# TL200.net
KiCad netlist of a schematic drawn in Altium Designer
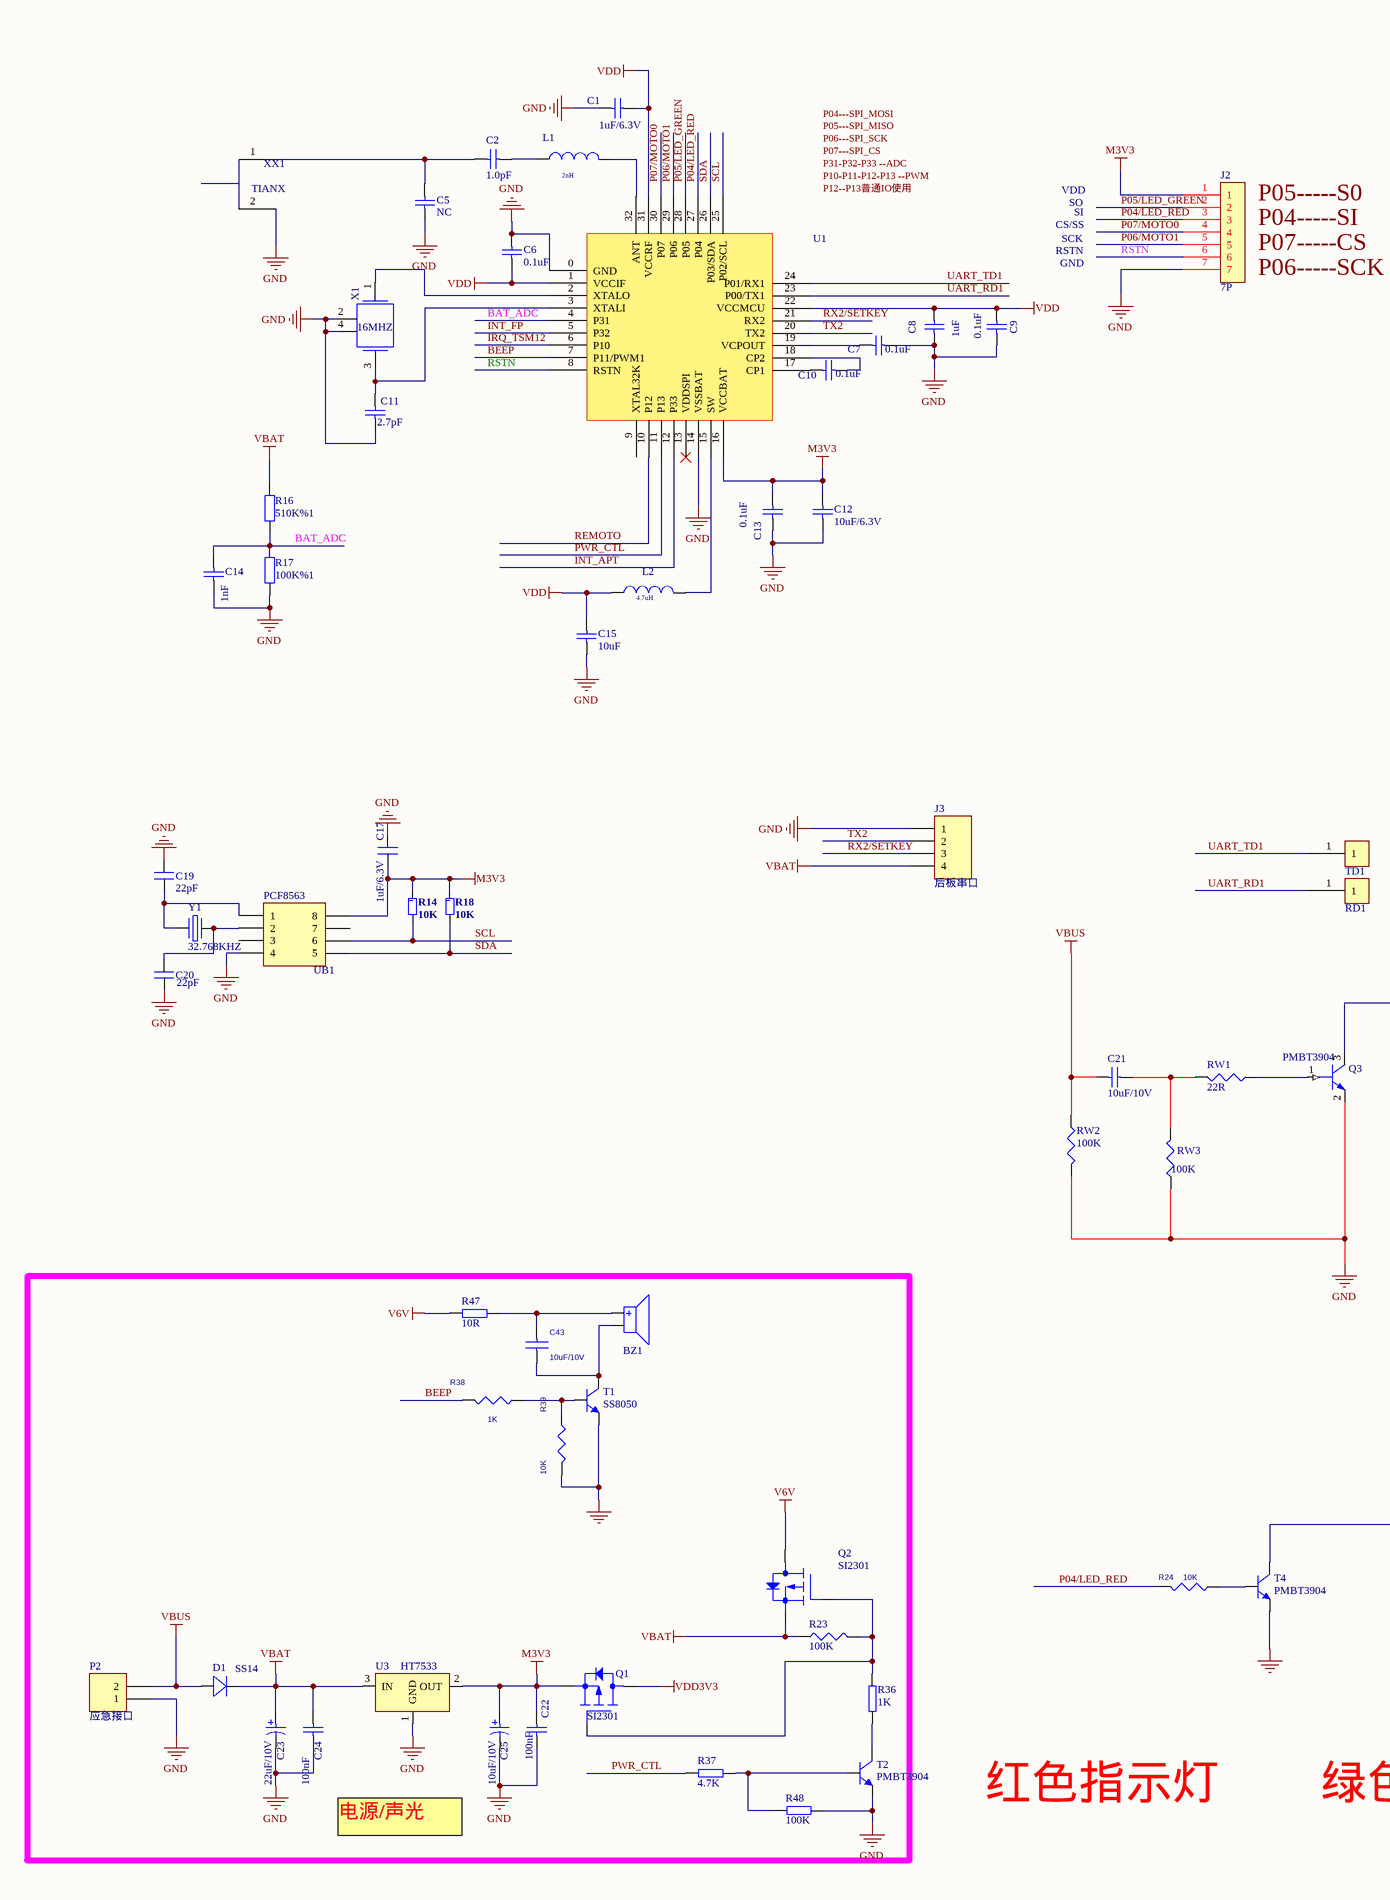
[diagram p0: TL200蓝牙主板.SchDoc, left]
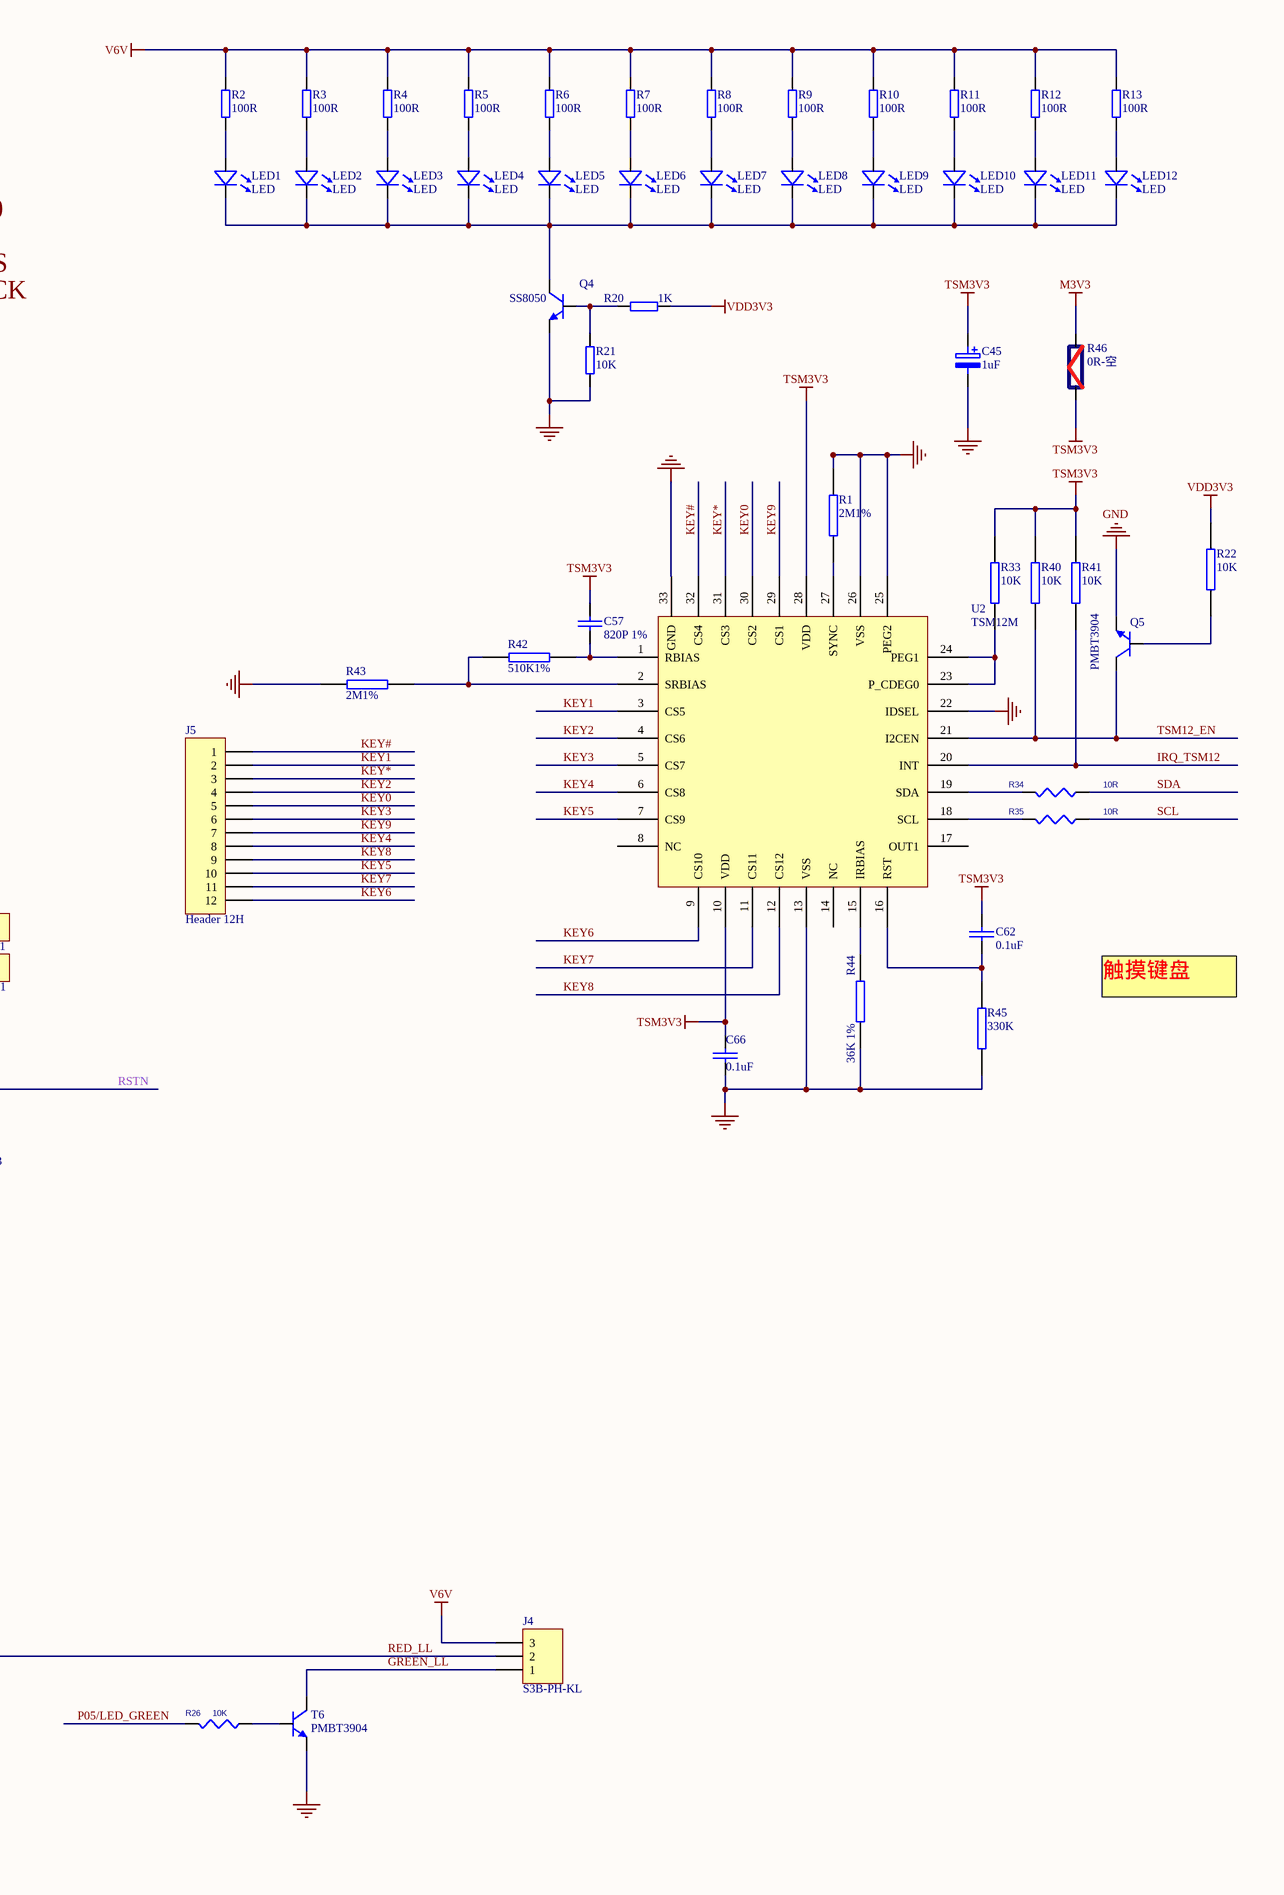
[diagram p1: TL200蓝牙主板.SchDoc, right]

(export (version "E")
  (design (tool "Eeschema 10.0.6"))
  (components
    (comp (ref "BZ1")
      (value "BUZZER")
      (footprint "BUZZER_D93_L40")
      (description "Buzzer")
      (libsource (lib "MyLibrary") (part "BUZZER"))
    )
    (comp (ref "C1")
      (value "1uF/6.3V")
      (footprint "LC-0402_C")
      (description "Capacitor")
      (fields (field (name "PUBLISHER") "Altium Limited"))
      (libsource (lib "MySchlib") (part "Cap"))
    )
    (comp (ref "C2")
      (value "1.0pF")
      (footprint "LC-0402_C")
      (description "Capacitor")
      (fields (field (name "PUBLISHER") "Altium Limited"))
      (libsource (lib "MySchlib") (part "Cap"))
    )
    (comp (ref "C5")
      (value "NC")
      (footprint "LC-0402_C")
      (description "Capacitor")
      (fields (field (name "PUBLISHER") "Altium Limited"))
      (libsource (lib "MySchlib") (part "Cap"))
    )
    (comp (ref "C6")
      (value "0.1uF")
      (footprint "LC-0402_C")
      (description "Capacitor")
      (fields (field (name "PUBLISHER") "Altium Limited"))
      (libsource (lib "MySchlib") (part "Cap"))
    )
    (comp (ref "C7")
      (value "0.1uF")
      (footprint "LC-0402_C")
      (description "Capacitor")
      (fields (field (name "PUBLISHER") "Altium Limited"))
      (libsource (lib "MySchlib") (part "Cap"))
    )
    (comp (ref "C8")
      (value "1uF")
      (footprint "LC-0402_C")
      (description "Capacitor")
      (fields (field (name "PUBLISHER") "Altium Limited"))
      (libsource (lib "MySchlib") (part "Cap"))
    )
    (comp (ref "C9")
      (value "0.1uF")
      (footprint "LC-0402_C")
      (description "Capacitor")
      (fields (field (name "PUBLISHER") "Altium Limited"))
      (libsource (lib "MySchlib") (part "Cap"))
    )
    (comp (ref "C10")
      (value "0.1uF")
      (footprint "LC-0402_C")
      (description "Capacitor")
      (fields (field (name "PUBLISHER") "Altium Limited"))
      (libsource (lib "MySchlib") (part "Cap"))
    )
    (comp (ref "C11")
      (value "2.7pF")
      (footprint "LC-0402_C")
      (description "Capacitor")
      (fields (field (name "PUBLISHER") "Altium Limited"))
      (libsource (lib "MySchlib") (part "Cap"))
    )
    (comp (ref "C12")
      (value "10uF/6.3V")
      (footprint "LC-0603_C")
      (description "Capacitor")
      (fields (field (name "PUBLISHER") "Altium Limited"))
      (libsource (lib "MySchlib") (part "Cap"))
    )
    (comp (ref "C13")
      (value "0.1uF")
      (footprint "LC-0402_C")
      (description "Capacitor")
      (fields (field (name "PUBLISHER") "Altium Limited"))
      (libsource (lib "MySchlib") (part "Cap"))
    )
    (comp (ref "C14")
      (value "1nF")
      (footprint "LC-0402_C")
      (description "Capacitor, Ceramic")
      (fields (field (name "TOLERANCE") "5 %"))
      (libsource (lib "MyLibrary") (part "CAP-NP"))
    )
    (comp (ref "C15")
      (value "10uF")
      (footprint "LC-0402_C")
      (description "Capacitor")
      (fields (field (name "PUBLISHER") "Altium Limited"))
      (libsource (lib "MySchlib") (part "Cap"))
    )
    (comp (ref "C17") (value "1uF/6.3V") (footprint "LC-0603_C") (libsource (lib "自建元件库") (part "C")))
    (comp (ref "C19") (value "22pF") (footprint "LC-0603_C") (libsource (lib "自建元件库") (part "C")))
    (comp (ref "C20") (value "22pF") (footprint "LC-0603_C") (libsource (lib "自建元件库") (part "C")))
    (comp (ref "C21")
      (value "10uF/10V")
      (footprint "LC-0603_C")
      (description "Capacitor, Ceramic")
      (fields (field (name "TOLERANCE") "5 %"))
      (libsource (lib "MyLibrary") (part "CAP-NP"))
    )
    (comp (ref "C22")
      (value "100nF")
      (footprint "LC-0603_C")
      (description "Capacitor, Ceramic")
      (fields (field (name "TOLERANCE") "5 %"))
      (libsource (lib "MyLibrary") (part "CAP-NP"))
    )
    (comp (ref "C23")
      (value "22uF/10V")
      (footprint "LC-0805_C")
      (description "Capacitor, tolerance ±20%")
      (libsource (lib "MySchLib") (part "CAP-P"))
    )
    (comp (ref "C24")
      (value "100nF")
      (footprint "LC-0603_C")
      (description "Capacitor, Ceramic")
      (fields (field (name "TOLERANCE") "5 %"))
      (libsource (lib "MyLibrary") (part "CAP-NP"))
    )
    (comp (ref "C25")
      (value "10uF/10V")
      (footprint "LC-0805_C")
      (description "Capacitor, tolerance ±20%")
      (libsource (lib "MySchLib") (part "CAP-P"))
    )
    (comp (ref "C43") (value "10uF/10V") (footprint "LC-0603_C") (libsource (lib "*") (part "C_0_Dup1")))
    (comp (ref "C45")
      (value "1uF")
      (footprint "LC-0603_C")
      (description "Electrolytic Capacitor")
      (libsource (lib "*") (part "C-C型"))
    )
    (comp (ref "C57")
      (value "820P 1%")
      (footprint "LC-0402_C")
      (description "Capacitor")
      (libsource (lib "*") (part "CAP"))
    )
    (comp (ref "C62")
      (value "0.1uF")
      (footprint "LC-0402_C")
      (description "Capacitor")
      (libsource (lib "*") (part "CAP"))
    )
    (comp (ref "C66")
      (value "0.1uF")
      (footprint "LC-0402_C")
      (description "Capacitor")
      (libsource (lib "*") (part "CAP"))
    )
    (comp (ref "D1") (value "SS14") (footprint "DO-214AA") (libsource (lib "MySch") (part "D")))
    (comp (ref "J2") (value "7P") (footprint "7P-2.0MM") (libsource (lib "保险箱STM32") (part "7P")))
    (comp (ref "J3")
      (value "后板串口")
      (footprint "4P-2.0XX")
      (description "Header, 4-Pin, Right Angle")
      (fields (field (name "PUBLISHER") "Altium Limited"))
      (libsource (lib "Miscellaneous Connectors") (part "Header 4H"))
    )
    (comp (ref "J4")
      (value "S3B-PH-KL")
      (footprint "3P-1.25mm-SMT")
      (description "Header, 3-Pin")
      (fields (field (name "PUBLISHER") "Altium Limited"))
      (libsource (lib "Miscellaneous Connectors") (part "Header 3"))
    )
    (comp (ref "J5")
      (value "Header 12H")
      (footprint "6P*2*1.27MM_1")
      (description "Header, 12-Pin, Right Angle")
      (fields (field (name "PUBLISHER") "Altium Limited"))
      (libsource (lib "Miscellaneous Connectors") (part "Header 12H"))
    )
    (comp (ref "L1")
      (value "2nH")
      (footprint "LC-0402_L")
      (description "Power Inductor, 4.7uH, 0.7A, 260mR DCR")
      (fields
        (field (name "XMOS PART NUMBER") "E-09-0011")
        (field (name "MANUFACTURER") "Taiyo Yuden")
        (field (name "PART CREATOR") "JG")
        (field (name "APPROVED") "NO")
      )
      (libsource (lib "MySchlib") (part "INDUCTOR"))
    )
    (comp (ref "L2")
      (value "4.7uH")
      (footprint "LC-0603_L")
      (description "Power Inductor, 4.7uH, 0.7A, 260mR DCR")
      (fields
        (field (name "XMOS PART NUMBER") "E-09-0011")
        (field (name "MANUFACTURER") "Taiyo Yuden")
        (field (name "PART CREATOR") "JG")
        (field (name "APPROVED") "NO")
      )
      (libsource (lib "MySchlib") (part "INDUCTOR"))
    )
    (comp (ref "LED1") (value "LED") (footprint "0603LED") (libsource (lib "MyLibrary") (part "LED")))
    (comp (ref "LED2") (value "LED") (footprint "0603LED") (libsource (lib "MyLibrary") (part "LED")))
    (comp (ref "LED3") (value "LED") (footprint "0603LED") (libsource (lib "MyLibrary") (part "LED")))
    (comp (ref "LED4") (value "LED") (footprint "0603LED") (libsource (lib "MyLibrary") (part "LED")))
    (comp (ref "LED5") (value "LED") (footprint "0603LED") (libsource (lib "MyLibrary") (part "LED")))
    (comp (ref "LED6") (value "LED") (footprint "0603LED") (libsource (lib "MyLibrary") (part "LED")))
    (comp (ref "LED7") (value "LED") (footprint "0603LED") (libsource (lib "MyLibrary") (part "LED")))
    (comp (ref "LED8") (value "LED") (footprint "0603LED") (libsource (lib "MyLibrary") (part "LED")))
    (comp (ref "LED9") (value "LED") (footprint "0603LED") (libsource (lib "MyLibrary") (part "LED")))
    (comp (ref "LED10") (value "LED") (footprint "0603LED") (libsource (lib "MyLibrary") (part "LED")))
    (comp (ref "LED11") (value "LED") (footprint "0603LED") (libsource (lib "MyLibrary") (part "LED")))
    (comp (ref "LED12") (value "LED") (footprint "0603LED") (libsource (lib "MyLibrary") (part "LED")))
    (comp (ref "P2")
      (value "应急接口")
      (footprint "2PIN-2.0")
      (description "Header, 2-Pin")
      (fields (field (name "PUBLISHER") "Altium Limited"))
      (libsource (lib "Miscellaneous Connectors") (part "Header 2"))
    )
    (comp (ref "Q1")
      (value "SI2301")
      (footprint "SOT-23 - GDS")
      (libsource (lib "*") (part "PWRMOSFET_EP_DGS_0"))
    )
    (comp (ref "Q2")
      (value "SI2301")
      (footprint "SOT-23 - GDS")
      (libsource (lib "*") (part "PWRMOSFET_EP_DGS_0"))
    )
    (comp (ref "Q3") (value "PMBT3904") (footprint "SOT-23-3L") (libsource (lib "*") (part "PMBT3904")))
    (comp (ref "Q4")
      (value "SS8050")
      (footprint "SOT-23-3L")
      (description "Bipolar Junction Transistor")
      (libsource (lib "MyLibrary") (part "NPN_BJT"))
    )
    (comp (ref "Q5")
      (value "PMBT3904")
      (footprint "SOT-23-3L")
      (description "Bipolar Junction Transistor")
      (libsource (lib "MyLibrary") (part "NPN_BJT"))
    )
    (comp (ref "R1") (value "2M1%") (footprint "LC-0402_R") (libsource (lib "*") (part "RES2")))
    (comp (ref "R2") (value "100R") (footprint "LC-0603_R") (libsource (lib "MySch") (part "R")))
    (comp (ref "R3") (value "100R") (footprint "LC-0603_R") (libsource (lib "MySch") (part "R")))
    (comp (ref "R4") (value "100R") (footprint "LC-0603_R") (libsource (lib "MySch") (part "R")))
    (comp (ref "R5") (value "100R") (footprint "LC-0603_R") (libsource (lib "MySch") (part "R")))
    (comp (ref "R6") (value "100R") (footprint "LC-0603_R") (libsource (lib "MySch") (part "R")))
    (comp (ref "R7") (value "100R") (footprint "LC-0603_R") (libsource (lib "MySch") (part "R")))
    (comp (ref "R8") (value "100R") (footprint "LC-0603_R") (libsource (lib "MySch") (part "R")))
    (comp (ref "R9") (value "100R") (footprint "LC-0603_R") (libsource (lib "MySch") (part "R")))
    (comp (ref "R10") (value "100R") (footprint "LC-0603_R") (libsource (lib "MySch") (part "R")))
    (comp (ref "R11") (value "100R") (footprint "LC-0603_R") (libsource (lib "MySch") (part "R")))
    (comp (ref "R12") (value "100R") (footprint "LC-0603_R") (libsource (lib "MySch") (part "R")))
    (comp (ref "R13") (value "100R") (footprint "LC-0603_R") (libsource (lib "MySch") (part "R")))
    (comp (ref "R14")
      (value "10K")
      (footprint "LC-0603_R")
      (description "Resistor")
      (libsource (lib "S3C2416") (part "RES_0603A"))
    )
    (comp (ref "R16")
      (value "510K%1")
      (footprint "LC-0402_R")
      (description "Resistor")
      (libsource (lib "MyLibrary") (part "Res2"))
    )
    (comp (ref "R17")
      (value "100K%1")
      (footprint "LC-0402_R")
      (description "Resistor")
      (libsource (lib "MyLibrary") (part "Res2"))
    )
    (comp (ref "R18")
      (value "10K")
      (footprint "LC-0603_R")
      (description "Resistor")
      (libsource (lib "S3C2416") (part "RES_0603A"))
    )
    (comp (ref "R20") (value "1K") (footprint "LC-0603_R") (libsource (lib "MySch") (part "R")))
    (comp (ref "R21") (value "10K") (footprint "LC-0603_R") (libsource (lib "MySch") (part "R")))
    (comp (ref "R22") (value "10K") (footprint "LC-0603_R") (libsource (lib "*") (part "RES2")))
    (comp (ref "R23") (value "100K") (footprint "LC-0603_R") (libsource (lib "*") (part "R")))
    (comp (ref "R24") (value "10K") (footprint "LC-0603_R") (libsource (lib "*") (part "RES")))
    (comp (ref "R26") (value "10K") (footprint "LC-0603_R") (libsource (lib "*") (part "RES")))
    (comp (ref "R33") (value "10K") (footprint "LC-0402_R") (libsource (lib "*") (part "RES2")))
    (comp (ref "R34") (value "10R") (footprint "LC-0402_R") (libsource (lib "*") (part "R_Dup1")))
    (comp (ref "R35") (value "10R") (footprint "LC-0402_R") (libsource (lib "*") (part "R_Dup1")))
    (comp (ref "R36") (value "1K") (footprint "LC-0603_R") (libsource (lib "MySch") (part "R")))
    (comp (ref "R37") (value "4.7K") (footprint "LC-0603_R") (libsource (lib "MySch") (part "R")))
    (comp (ref "R38") (value "1K") (footprint "LC-0603_R") (libsource (lib "*") (part "R_Dup1")))
    (comp (ref "R39") (value "10K") (footprint "LC-0603_R") (libsource (lib "*") (part "R_Dup1")))
    (comp (ref "R40") (value "10K") (footprint "LC-0402_R") (libsource (lib "*") (part "RES2")))
    (comp (ref "R41") (value "10K") (footprint "LC-0402_R") (libsource (lib "*") (part "RES2")))
    (comp (ref "R42") (value "510K1%") (footprint "LC-0402_R") (libsource (lib "*") (part "RES2")))
    (comp (ref "R43") (value "2M1%") (footprint "LC-0402_R") (libsource (lib "*") (part "RES2")))
    (comp (ref "R44") (value "36K 1%") (footprint "LC-0402_R") (libsource (lib "*") (part "RES2")))
    (comp (ref "R45") (value "330K") (footprint "LC-0402_R") (libsource (lib "*") (part "RES2")))
    (comp (ref "R46") (value "0R-空") (footprint "LC-0603_R") (libsource (lib "MYSchlib") (part "POWER-R")))
    (comp (ref "R47") (value "10R") (footprint "LC-0603_R") (libsource (lib "MySch") (part "R")))
    (comp (ref "R48") (value "100K") (footprint "LC-0603_R") (libsource (lib "MySch") (part "R")))
    (comp (ref "RD1") (value "DC+") (footprint "TP-THD - 1mm") (libsource (lib "TL200蓝牙主板") (part "con1")))
    (comp (ref "RW1") (value "22R") (footprint "LC-0603_R") (libsource (lib "*") (part "R")))
    (comp (ref "RW2") (value "100K") (footprint "LC-0603_R") (libsource (lib "*") (part "R")))
    (comp (ref "RW3") (value "100K") (footprint "LC-0603_R") (libsource (lib "*") (part "R")))
    (comp (ref "T1")
      (value "SS8050")
      (footprint "SOT-23-3L")
      (description "Bipolar Junction Transistor")
      (libsource (lib "MyLibrary") (part "NPN_BJT"))
    )
    (comp (ref "T2")
      (value "PMBT3904")
      (footprint "SOT-23-3L")
      (description "Bipolar Junction Transistor")
      (libsource (lib "MyLibrary") (part "NPN_BJT"))
    )
    (comp (ref "T4")
      (value "PMBT3904")
      (footprint "SOT-23-3L")
      (description "Bipolar Junction Transistor")
      (libsource (lib "MyLibrary") (part "NPN_BJT"))
    )
    (comp (ref "T6")
      (value "PMBT3904")
      (footprint "SOT-23-3L")
      (description "Bipolar Junction Transistor")
      (libsource (lib "MyLibrary") (part "NPN_BJT"))
    )
    (comp (ref "TD1") (value "DC+") (footprint "TP-THD - 1mm") (libsource (lib "TL200蓝牙主板") (part "con1")))
    (comp (ref "U1")
      (value "BK3431Q")
      (footprint "QFN32_4*4*0.4")
      (libsource (lib "TL200蓝牙主板") (part "BK3431Q"))
    )
    (comp (ref "U2") (value "TSM12M") (footprint "ADS_TMS12") (libsource (lib "TL200蓝牙主板") (part "TSM12M")))
    (comp (ref "U3") (value "HT7533") (footprint "SOT-23-3L") (libsource (lib "*") (part "XC6206P302M")))
    (comp (ref "UB1") (value "PCF8563") (footprint "SOP8") (libsource (lib "MySch") (part "IC8")))
    (comp (ref "X1")
      (value "16MHZ")
      (footprint "XTAL3225")
      (fields
        (field (name "XMOS PART NUMBER") "E-07-0030")
        (field (name "MANUFACTURER") "Abracon")
        (field (name "MANUFACTURER PART NUMBER") "ABLS-24.000MHz-B4")
        (field (name "PART CREATOR") "JG")
        (field (name "APPROVED") "NO")
      )
      (libsource (lib "MySchlib") (part "OSC"))
    )
    (comp (ref "XX1")
      (value "TIANX")
      (footprint "BT_NAMI_1")
      (libsource (lib "885阿里云PCB_Project1") (part "TIANX"))
    )
    (comp (ref "Y1") (value "32.768KHZ") (footprint "晶振-9") (libsource (lib "MySch") (part "晶振")))
  )
  (nets
    (net (code "1") (name "/BAT_ADC") (class "Default")
      (node (ref "C14") (pin "2") (pinfunction "2_2") (pintype "passive"))
      (node (ref "R16") (pin "2") (pinfunction "2_2") (pintype "passive"))
      (node (ref "R17") (pin "1") (pinfunction "1_1") (pintype "passive"))
      (node (ref "U1") (pin "4") (pinfunction "P31_4") (pintype "passive"))
    )
    (net (code "2") (name "/BEEP") (class "Default")
      (node (ref "R38") (pin "2") (pinfunction "2_2") (pintype "passive"))
      (node (ref "U1") (pin "7") (pinfunction "P11/PWM1_7") (pintype "passive"))
    )
    (net (code "3") (name "/GREEN_LL") (class "Default")
      (node (ref "J4") (pin "1") (pinfunction "1_1") (pintype "passive"))
      (node (ref "T6") (pin "3") (pinfunction "3_3") (pintype "passive"))
    )
    (net (code "4") (name "/INT_APT") (class "Default")
      (node (ref "U1") (pin "12") (pinfunction "P33_12") (pintype "passive"))
    )
    (net (code "5") (name "/INT_FP") (class "Default")
      (node (ref "U1") (pin "5") (pinfunction "P32_5") (pintype "passive"))
    )
    (net (code "6") (name "/IRQ_TSM12") (class "Default")
      (node (ref "R41") (pin "1") (pinfunction "1_1") (pintype "passive"))
      (node (ref "U1") (pin "6") (pinfunction "P10_6") (pintype "passive"))
      (node (ref "U2") (pin "20") (pinfunction "INT_20") (pintype "passive"))
    )
    (net (code "7") (name "/KEY#") (class "Default")
      (node (ref "J5") (pin "1") (pinfunction "1_1") (pintype "passive"))
      (node (ref "U2") (pin "32") (pinfunction "CS4_32") (pintype "passive"))
    )
    (net (code "8") (name "/KEY*") (class "Default")
      (node (ref "J5") (pin "3") (pinfunction "3_3") (pintype "passive"))
      (node (ref "U2") (pin "31") (pinfunction "CS3_31") (pintype "passive"))
    )
    (net (code "9") (name "/KEY0") (class "Default")
      (node (ref "J5") (pin "5") (pinfunction "5_5") (pintype "passive"))
      (node (ref "U2") (pin "30") (pinfunction "CS2_30") (pintype "passive"))
    )
    (net (code "10") (name "/KEY1") (class "Default")
      (node (ref "J5") (pin "2") (pinfunction "2_2") (pintype "passive"))
      (node (ref "U2") (pin "3") (pinfunction "CS5_3") (pintype "passive"))
    )
    (net (code "11") (name "/KEY2") (class "Default")
      (node (ref "J5") (pin "4") (pinfunction "4_4") (pintype "passive"))
      (node (ref "U2") (pin "4") (pinfunction "CS6_4") (pintype "passive"))
    )
    (net (code "12") (name "/KEY3") (class "Default")
      (node (ref "J5") (pin "6") (pinfunction "6_6") (pintype "passive"))
      (node (ref "U2") (pin "5") (pinfunction "CS7_5") (pintype "passive"))
    )
    (net (code "13") (name "/KEY4") (class "Default")
      (node (ref "J5") (pin "8") (pinfunction "8_8") (pintype "passive"))
      (node (ref "U2") (pin "6") (pinfunction "CS8_6") (pintype "passive"))
    )
    (net (code "14") (name "/KEY5") (class "Default")
      (node (ref "J5") (pin "10") (pinfunction "10_10") (pintype "passive"))
      (node (ref "U2") (pin "7") (pinfunction "CS9_7") (pintype "passive"))
    )
    (net (code "15") (name "/KEY6") (class "Default")
      (node (ref "J5") (pin "12") (pinfunction "12_12") (pintype "passive"))
      (node (ref "U2") (pin "9") (pinfunction "CS10_9") (pintype "passive"))
    )
    (net (code "16") (name "/KEY7") (class "Default")
      (node (ref "J5") (pin "11") (pinfunction "11_11") (pintype "passive"))
      (node (ref "U2") (pin "11") (pinfunction "CS11_11") (pintype "passive"))
    )
    (net (code "17") (name "/KEY8") (class "Default")
      (node (ref "J5") (pin "9") (pinfunction "9_9") (pintype "passive"))
      (node (ref "U2") (pin "12") (pinfunction "CS12_12") (pintype "passive"))
    )
    (net (code "18") (name "/KEY9") (class "Default")
      (node (ref "J5") (pin "7") (pinfunction "7_7") (pintype "passive"))
      (node (ref "U2") (pin "29") (pinfunction "CS1_29") (pintype "passive"))
    )
    (net (code "19") (name "/P04{slash}LED_RED") (class "Default")
      (node (ref "J2") (pin "3") (pinfunction "3_3") (pintype "passive"))
      (node (ref "R24") (pin "2") (pinfunction "2_2") (pintype "passive"))
      (node (ref "U1") (pin "27") (pinfunction "P04_27") (pintype "passive"))
    )
    (net (code "20") (name "/P05{slash}LED_GREEN") (class "Default")
      (node (ref "J2") (pin "2") (pinfunction "2_2") (pintype "passive"))
      (node (ref "R26") (pin "2") (pinfunction "2_2") (pintype "passive"))
      (node (ref "U1") (pin "28") (pinfunction "P05_28") (pintype "passive"))
    )
    (net (code "21") (name "/P06{slash}MOTO1") (class "Default")
      (node (ref "J2") (pin "5") (pinfunction "5_5") (pintype "passive"))
      (node (ref "U1") (pin "29") (pinfunction "P06_29") (pintype "passive"))
    )
    (net (code "22") (name "/P07{slash}MOTO0") (class "Default")
      (node (ref "J2") (pin "4") (pinfunction "4_4") (pintype "passive"))
      (node (ref "U1") (pin "30") (pinfunction "P07_30") (pintype "passive"))
    )
    (net (code "23") (name "/PWR_CTL") (class "Default")
      (node (ref "R37") (pin "1") (pintype "passive"))
      (node (ref "U1") (pin "11") (pinfunction "P13_11") (pintype "passive"))
    )
    (net (code "24") (name "/RED_LL") (class "Default")
      (node (ref "J4") (pin "2") (pinfunction "2_2") (pintype "passive"))
      (node (ref "T4") (pin "3") (pinfunction "3_3") (pintype "passive"))
    )
    (net (code "25") (name "/REMOTO") (class "Default")
      (node (ref "U1") (pin "10") (pinfunction "P12_10") (pintype "passive"))
    )
    (net (code "26") (name "/RSTN") (class "Default")
      (node (ref "J2") (pin "6") (pinfunction "6_6") (pintype "passive"))
      (node (ref "Q3") (pin "3") (pinfunction "3_3") (pintype "passive"))
      (node (ref "U1") (pin "8") (pinfunction "RSTN_8") (pintype "passive"))
    )
    (net (code "27") (name "/RX2{slash}SETKEY") (class "Default")
      (node (ref "J3") (pin "3") (pinfunction "3_3") (pintype "passive"))
      (node (ref "U1") (pin "21") (pinfunction "RX2_21") (pintype "passive"))
    )
    (net (code "28") (name "/SCL") (class "Default")
      (node (ref "R14") (pin "2") (pinfunction "2_2") (pintype "passive"))
      (node (ref "R35") (pin "1") (pinfunction "1_1") (pintype "passive"))
      (node (ref "U1") (pin "25") (pinfunction "P02/SCL_25") (pintype "passive"))
      (node (ref "UB1") (pin "6") (pinfunction "6_6") (pintype "passive"))
    )
    (net (code "29") (name "/SDA") (class "Default")
      (node (ref "R18") (pin "2") (pinfunction "2_2") (pintype "passive"))
      (node (ref "R34") (pin "1") (pinfunction "1_1") (pintype "passive"))
      (node (ref "U1") (pin "26") (pinfunction "P03/SDA_26") (pintype "passive"))
      (node (ref "UB1") (pin "5") (pinfunction "5_5") (pintype "passive"))
    )
    (net (code "30") (name "/TSM12_EN") (class "Default")
      (node (ref "Q5") (pin "3") (pinfunction "3_3") (pintype "passive"))
      (node (ref "R40") (pin "1") (pinfunction "1_1") (pintype "passive"))
      (node (ref "U2") (pin "21") (pinfunction "I2CEN_21") (pintype "passive"))
    )
    (net (code "31") (name "/TX2") (class "Default")
      (node (ref "J3") (pin "2") (pinfunction "2_2") (pintype "passive"))
      (node (ref "U1") (pin "20") (pinfunction "TX2_20") (pintype "passive"))
    )
    (net (code "32") (name "/UART_RD1") (class "Default")
      (node (ref "RD1") (pin "1") (pinfunction "1_1") (pintype "passive"))
      (node (ref "U1") (pin "23") (pinfunction "P00/TX1_23") (pintype "passive"))
    )
    (net (code "33") (name "/UART_TD1") (class "Default")
      (node (ref "TD1") (pin "1") (pinfunction "1_1") (pintype "passive"))
      (node (ref "U1") (pin "24") (pinfunction "P01/RX1_24") (pintype "passive"))
    )
    (net (code "34") (name "GND") (class "Default")
      (node (ref "C1") (pin "1") (pinfunction "1_1") (pintype "passive"))
      (node (ref "C11") (pin "1") (pinfunction "1_1") (pintype "passive"))
      (node (ref "C12") (pin "2") (pinfunction "2_2") (pintype "passive"))
      (node (ref "C13") (pin "2") (pinfunction "2_2") (pintype "passive"))
      (node (ref "C14") (pin "1") (pinfunction "1_1") (pintype "passive"))
      (node (ref "C15") (pin "1") (pinfunction "1_1") (pintype "passive"))
      (node (ref "C17") (pin "2") (pintype "passive"))
      (node (ref "C19") (pin "2") (pintype "passive"))
      (node (ref "C20") (pin "1") (pintype "passive"))
      (node (ref "C22") (pin "2") (pinfunction "2_2") (pintype "passive"))
      (node (ref "C23") (pin "2") (pinfunction "2_2") (pintype "passive"))
      (node (ref "C24") (pin "2") (pinfunction "2_2") (pintype "passive"))
      (node (ref "C25") (pin "2") (pinfunction "2_2") (pintype "passive"))
      (node (ref "C45") (pin "2") (pinfunction "2_2") (pintype "passive"))
      (node (ref "C5") (pin "1") (pinfunction "1_1") (pintype "passive"))
      (node (ref "C6") (pin "1") (pinfunction "1_1") (pintype "passive"))
      (node (ref "C66") (pin "1") (pinfunction "1_1") (pintype "passive"))
      (node (ref "C7") (pin "2") (pinfunction "2_2") (pintype "passive"))
      (node (ref "C8") (pin "1") (pinfunction "1_1") (pintype "passive"))
      (node (ref "C9") (pin "1") (pinfunction "1_1") (pintype "passive"))
      (node (ref "J2") (pin "7") (pinfunction "7_7") (pintype "passive"))
      (node (ref "J3") (pin "1") (pinfunction "1_1") (pintype "passive"))
      (node (ref "P2") (pin "1") (pinfunction "1_1") (pintype "passive"))
      (node (ref "Q3") (pin "2") (pinfunction "2_2") (pintype "passive"))
      (node (ref "Q4") (pin "2") (pinfunction "2_2") (pintype "passive"))
      (node (ref "Q5") (pin "2") (pinfunction "2_2") (pintype "passive"))
      (node (ref "R1") (pin "2") (pinfunction "2_2") (pintype "passive"))
      (node (ref "R17") (pin "2") (pinfunction "2_2") (pintype "passive"))
      (node (ref "R21") (pin "1") (pintype "passive"))
      (node (ref "R39") (pin "2") (pinfunction "2_2") (pintype "passive"))
      (node (ref "R43") (pin "1") (pinfunction "1_1") (pintype "passive"))
      (node (ref "R44") (pin "1") (pinfunction "1_1") (pintype "passive"))
      (node (ref "R45") (pin "1") (pinfunction "1_1") (pintype "passive"))
      (node (ref "R48") (pin "1") (pintype "passive"))
      (node (ref "RW2") (pin "2") (pinfunction "2_2") (pintype "passive"))
      (node (ref "RW3") (pin "1") (pinfunction "1_1") (pintype "passive"))
      (node (ref "T1") (pin "2") (pinfunction "2_2") (pintype "passive"))
      (node (ref "T2") (pin "2") (pinfunction "2_2") (pintype "passive"))
      (node (ref "T4") (pin "2") (pinfunction "2_2") (pintype "passive"))
      (node (ref "T6") (pin "2") (pinfunction "2_2") (pintype "passive"))
      (node (ref "U1") (pin "0") (pinfunction "GND_0") (pintype "passive"))
      (node (ref "U1") (pin "14") (pinfunction "VSSBAT_14") (pintype "passive"))
      (node (ref "U2") (pin "13") (pinfunction "VSS_13") (pintype "passive"))
      (node (ref "U2") (pin "22") (pinfunction "IDSEL_22") (pintype "passive"))
      (node (ref "U2") (pin "25") (pinfunction "PEG2_25") (pintype "passive"))
      (node (ref "U2") (pin "26") (pinfunction "VSS_26") (pintype "passive"))
      (node (ref "U2") (pin "33") (pinfunction "GND_33") (pintype "passive"))
      (node (ref "U3") (pin "1") (pinfunction "GND_1") (pintype "passive"))
      (node (ref "UB1") (pin "4") (pinfunction "4_4") (pintype "passive"))
      (node (ref "X1") (pin "2") (pintype "passive"))
      (node (ref "X1") (pin "4") (pintype "passive"))
      (node (ref "XX1") (pin "2") (pinfunction "2_2") (pintype "passive"))
    )
    (net (code "35") (name "M3V3") (class "Default")
      (node (ref "C12") (pin "1") (pinfunction "1_1") (pintype "passive"))
      (node (ref "C13") (pin "1") (pinfunction "1_1") (pintype "passive"))
      (node (ref "C17") (pin "1") (pintype "passive"))
      (node (ref "C22") (pin "1") (pinfunction "1_1") (pintype "passive"))
      (node (ref "C25") (pin "1") (pinfunction "1_1") (pintype "passive"))
      (node (ref "J2") (pin "1") (pinfunction "1_1") (pintype "passive"))
      (node (ref "Q1") (pin "S") (pinfunction "SOURCE_S") (pintype "passive"))
      (node (ref "R14") (pin "1") (pinfunction "1_1") (pintype "passive"))
      (node (ref "R18") (pin "1") (pinfunction "1_1") (pintype "passive"))
      (node (ref "R46") (pin "2") (pinfunction "2_2") (pintype "passive"))
      (node (ref "U1") (pin "16") (pinfunction "VCCBAT_16") (pintype "passive"))
      (node (ref "U3") (pin "2") (pinfunction "OUT_2") (pintype "passive"))
      (node (ref "UB1") (pin "8") (pinfunction "8_8") (pintype "passive"))
    )
    (net (code "36") (name "Net-(BZ1-Pad1)") (class "Default")
      (node (ref "BZ1") (pin "1") (pintype "passive"))
      (node (ref "C43") (pin "2") (pinfunction "2_2") (pintype "passive"))
      (node (ref "R47") (pin "1") (pintype "passive"))
    )
    (net (code "37") (name "Net-(BZ1-Pad2)") (class "Default")
      (node (ref "BZ1") (pin "2") (pintype "passive"))
      (node (ref "C43") (pin "1") (pinfunction "1_1") (pintype "passive"))
      (node (ref "T1") (pin "3") (pinfunction "3_3") (pintype "passive"))
    )
    (net (code "38") (name "Net-(C2-Pad2)") (class "Default")
      (node (ref "C2") (pin "2") (pinfunction "2_2") (pintype "passive"))
      (node (ref "C5") (pin "2") (pinfunction "2_2") (pintype "passive"))
      (node (ref "XX1") (pin "1") (pinfunction "1_1") (pintype "passive"))
    )
    (net (code "39") (name "Net-(C19-Pad1)") (class "Default")
      (node (ref "C19") (pin "1") (pintype "passive"))
      (node (ref "UB1") (pin "1") (pinfunction "1_1") (pintype "passive"))
      (node (ref "Y1") (pin "1") (pintype "passive"))
    )
    (net (code "40") (name "Net-(C20-Pad2)") (class "Default")
      (node (ref "C20") (pin "2") (pintype "passive"))
      (node (ref "UB1") (pin "2") (pinfunction "2_2") (pintype "passive"))
      (node (ref "Y1") (pin "2") (pintype "passive"))
    )
    (net (code "41") (name "Net-(C21-Pad2)") (class "Default")
      (node (ref "C21") (pin "2") (pinfunction "2_2") (pintype "passive"))
      (node (ref "RW1") (pin "2") (pinfunction "2_2") (pintype "passive"))
      (node (ref "RW3") (pin "2") (pinfunction "2_2") (pintype "passive"))
    )
    (net (code "42") (name "Net-(L1-P1)") (class "Default")
      (node (ref "C2") (pin "1") (pinfunction "1_1") (pintype "passive"))
      (node (ref "L1") (pin "1") (pinfunction "P1_1") (pintype "passive"))
    )
    (net (code "43") (name "Net-(L1-P2)") (class "Default")
      (node (ref "L1") (pin "2") (pinfunction "P2_2") (pintype "passive"))
      (node (ref "U1") (pin "32") (pinfunction "ANT_32") (pintype "passive"))
    )
    (net (code "44") (name "Net-(L2-P2)") (class "Default")
      (node (ref "L2") (pin "2") (pinfunction "P2_2") (pintype "passive"))
      (node (ref "U1") (pin "15") (pinfunction "SW_15") (pintype "passive"))
    )
    (net (code "45") (name "Net-(LED1-a)") (class "Default")
      (node (ref "LED1") (pin "1") (pinfunction "a_1") (pintype "passive"))
      (node (ref "R2") (pin "1") (pintype "passive"))
    )
    (net (code "46") (name "Net-(LED1-k)") (class "Default")
      (node (ref "LED1") (pin "2") (pinfunction "k_2") (pintype "passive"))
      (node (ref "LED10") (pin "2") (pinfunction "k_2") (pintype "passive"))
      (node (ref "LED11") (pin "2") (pinfunction "k_2") (pintype "passive"))
      (node (ref "LED12") (pin "2") (pinfunction "k_2") (pintype "passive"))
      (node (ref "LED2") (pin "2") (pinfunction "k_2") (pintype "passive"))
      (node (ref "LED3") (pin "2") (pinfunction "k_2") (pintype "passive"))
      (node (ref "LED4") (pin "2") (pinfunction "k_2") (pintype "passive"))
      (node (ref "LED5") (pin "2") (pinfunction "k_2") (pintype "passive"))
      (node (ref "LED6") (pin "2") (pinfunction "k_2") (pintype "passive"))
      (node (ref "LED7") (pin "2") (pinfunction "k_2") (pintype "passive"))
      (node (ref "LED8") (pin "2") (pinfunction "k_2") (pintype "passive"))
      (node (ref "LED9") (pin "2") (pinfunction "k_2") (pintype "passive"))
      (node (ref "Q4") (pin "3") (pinfunction "3_3") (pintype "passive"))
    )
    (net (code "47") (name "Net-(LED2-a)") (class "Default")
      (node (ref "LED2") (pin "1") (pinfunction "a_1") (pintype "passive"))
      (node (ref "R3") (pin "1") (pintype "passive"))
    )
    (net (code "48") (name "Net-(LED3-a)") (class "Default")
      (node (ref "LED3") (pin "1") (pinfunction "a_1") (pintype "passive"))
      (node (ref "R4") (pin "1") (pintype "passive"))
    )
    (net (code "49") (name "Net-(LED4-a)") (class "Default")
      (node (ref "LED4") (pin "1") (pinfunction "a_1") (pintype "passive"))
      (node (ref "R5") (pin "1") (pintype "passive"))
    )
    (net (code "50") (name "Net-(LED5-a)") (class "Default")
      (node (ref "LED5") (pin "1") (pinfunction "a_1") (pintype "passive"))
      (node (ref "R6") (pin "1") (pintype "passive"))
    )
    (net (code "51") (name "Net-(LED6-a)") (class "Default")
      (node (ref "LED6") (pin "1") (pinfunction "a_1") (pintype "passive"))
      (node (ref "R7") (pin "1") (pintype "passive"))
    )
    (net (code "52") (name "Net-(LED7-a)") (class "Default")
      (node (ref "LED7") (pin "1") (pinfunction "a_1") (pintype "passive"))
      (node (ref "R8") (pin "1") (pintype "passive"))
    )
    (net (code "53") (name "Net-(LED8-a)") (class "Default")
      (node (ref "LED8") (pin "1") (pinfunction "a_1") (pintype "passive"))
      (node (ref "R9") (pin "1") (pintype "passive"))
    )
    (net (code "54") (name "Net-(LED9-a)") (class "Default")
      (node (ref "LED9") (pin "1") (pinfunction "a_1") (pintype "passive"))
      (node (ref "R10") (pin "1") (pintype "passive"))
    )
    (net (code "55") (name "Net-(LED10-a)") (class "Default")
      (node (ref "LED10") (pin "1") (pinfunction "a_1") (pintype "passive"))
      (node (ref "R11") (pin "1") (pintype "passive"))
    )
    (net (code "56") (name "Net-(LED11-a)") (class "Default")
      (node (ref "LED11") (pin "1") (pinfunction "a_1") (pintype "passive"))
      (node (ref "R12") (pin "1") (pintype "passive"))
    )
    (net (code "57") (name "Net-(LED12-a)") (class "Default")
      (node (ref "LED12") (pin "1") (pinfunction "a_1") (pintype "passive"))
      (node (ref "R13") (pin "1") (pintype "passive"))
    )
    (net (code "58") (name "Net-(Q1-GATE)") (class "Default")
      (node (ref "Q1") (pin "G") (pinfunction "GATE_G") (pintype "passive"))
      (node (ref "Q2") (pin "G") (pinfunction "GATE_G") (pintype "passive"))
      (node (ref "R23") (pin "2") (pinfunction "2_2") (pintype "passive"))
      (node (ref "R36") (pin "1") (pintype "passive"))
    )
    (net (code "59") (name "Net-(Q3-Pad1)") (class "Default")
      (node (ref "Q3") (pin "1") (pinfunction "1_1") (pintype "input"))
      (node (ref "RW1") (pin "1") (pinfunction "1_1") (pintype "passive"))
    )
    (net (code "60") (name "Net-(Q4-Pad1)") (class "Default")
      (node (ref "Q4") (pin "1") (pinfunction "1_1") (pintype "passive"))
      (node (ref "R20") (pin "1") (pintype "passive"))
      (node (ref "R21") (pin "2") (pintype "passive"))
    )
    (net (code "61") (name "Net-(Q5-Pad1)") (class "Default")
      (node (ref "Q5") (pin "1") (pinfunction "1_1") (pintype "passive"))
      (node (ref "R22") (pin "1") (pinfunction "1_1") (pintype "passive"))
    )
    (net (code "62") (name "Net-(R24-Pad1)") (class "Default")
      (node (ref "R24") (pin "1") (pinfunction "1_1") (pintype "passive"))
      (node (ref "T4") (pin "1") (pinfunction "1_1") (pintype "passive"))
    )
    (net (code "63") (name "Net-(R26-Pad1)") (class "Default")
      (node (ref "R26") (pin "1") (pinfunction "1_1") (pintype "passive"))
      (node (ref "T6") (pin "1") (pinfunction "1_1") (pintype "passive"))
    )
    (net (code "64") (name "Net-(R36-Pad2)") (class "Default")
      (node (ref "R36") (pin "2") (pintype "passive"))
      (node (ref "T2") (pin "3") (pinfunction "3_3") (pintype "passive"))
    )
    (net (code "65") (name "Net-(R37-Pad2)") (class "Default")
      (node (ref "R37") (pin "2") (pintype "passive"))
      (node (ref "R48") (pin "2") (pintype "passive"))
      (node (ref "T2") (pin "1") (pinfunction "1_1") (pintype "passive"))
    )
    (net (code "66") (name "Net-(R38-Pad1)") (class "Default")
      (node (ref "R38") (pin "1") (pinfunction "1_1") (pintype "passive"))
      (node (ref "R39") (pin "1") (pinfunction "1_1") (pintype "passive"))
      (node (ref "T1") (pin "1") (pinfunction "1_1") (pintype "passive"))
    )
    (net (code "67") (name "Net-(U1-CP1)") (class "Default")
      (node (ref "C10") (pin "1") (pinfunction "1_1") (pintype "passive"))
      (node (ref "U1") (pin "17") (pinfunction "CP1_17") (pintype "passive"))
    )
    (net (code "68") (name "Net-(U1-CP2)") (class "Default")
      (node (ref "C10") (pin "2") (pinfunction "2_2") (pintype "passive"))
      (node (ref "U1") (pin "18") (pinfunction "CP2_18") (pintype "passive"))
    )
    (net (code "69") (name "Net-(U1-VCPOUT)") (class "Default")
      (node (ref "C7") (pin "1") (pinfunction "1_1") (pintype "passive"))
      (node (ref "U1") (pin "19") (pinfunction "VCPOUT_19") (pintype "passive"))
    )
    (net (code "70") (name "Net-(U1-XTALI)") (class "Default")
      (node (ref "C11") (pin "2") (pinfunction "2_2") (pintype "passive"))
      (node (ref "U1") (pin "3") (pinfunction "XTALI_3") (pintype "passive"))
      (node (ref "X1") (pin "3") (pintype "passive"))
    )
    (net (code "71") (name "Net-(U1-XTALO)") (class "Default")
      (node (ref "U1") (pin "2") (pinfunction "XTALO_2") (pintype "passive"))
      (node (ref "X1") (pin "1") (pintype "passive"))
    )
    (net (code "72") (name "Net-(U2-IRBIAS)") (class "Default")
      (node (ref "R44") (pin "2") (pinfunction "2_2") (pintype "passive"))
      (node (ref "U2") (pin "15") (pinfunction "IRBIAS_15") (pintype "passive"))
    )
    (net (code "73") (name "Net-(U2-PEG1)") (class "Default")
      (node (ref "R33") (pin "1") (pinfunction "1_1") (pintype "passive"))
      (node (ref "U2") (pin "23") (pinfunction "P_CDEG0_23") (pintype "passive"))
      (node (ref "U2") (pin "24") (pinfunction "PEG1_24") (pintype "passive"))
    )
    (net (code "74") (name "Net-(U2-RBIAS)") (class "Default")
      (node (ref "C57") (pin "1") (pinfunction "1_1") (pintype "passive"))
      (node (ref "R42") (pin "2") (pinfunction "2_2") (pintype "passive"))
      (node (ref "U2") (pin "1") (pinfunction "RBIAS_1") (pintype "passive"))
    )
    (net (code "75") (name "Net-(U2-RST)") (class "Default")
      (node (ref "C62") (pin "1") (pinfunction "1_1") (pintype "passive"))
      (node (ref "R45") (pin "2") (pinfunction "2_2") (pintype "passive"))
      (node (ref "U2") (pin "16") (pinfunction "RST_16") (pintype "passive"))
    )
    (net (code "76") (name "Net-(U2-SCL)") (class "Default")
      (node (ref "R35") (pin "2") (pinfunction "2_2") (pintype "passive"))
      (node (ref "U2") (pin "18") (pinfunction "SCL_18") (pintype "passive"))
    )
    (net (code "77") (name "Net-(U2-SDA)") (class "Default")
      (node (ref "R34") (pin "2") (pinfunction "2_2") (pintype "passive"))
      (node (ref "U2") (pin "19") (pinfunction "SDA_19") (pintype "passive"))
    )
    (net (code "78") (name "Net-(U2-SRBIAS)") (class "Default")
      (node (ref "R42") (pin "1") (pinfunction "1_1") (pintype "passive"))
      (node (ref "R43") (pin "2") (pinfunction "2_2") (pintype "passive"))
      (node (ref "U2") (pin "2") (pinfunction "SRBIAS_2") (pintype "passive"))
    )
    (net (code "79") (name "Net-(U2-SYNC)") (class "Default")
      (node (ref "R1") (pin "1") (pinfunction "1_1") (pintype "passive"))
      (node (ref "U2") (pin "27") (pinfunction "SYNC_27") (pintype "passive"))
    )
    (net (code "80") (name "TSM3V3") (class "Default")
      (node (ref "C45") (pin "1") (pinfunction "1_1") (pintype "passive"))
      (node (ref "C57") (pin "2") (pinfunction "2_2") (pintype "passive"))
      (node (ref "C62") (pin "2") (pinfunction "2_2") (pintype "passive"))
      (node (ref "C66") (pin "2") (pinfunction "2_2") (pintype "passive"))
      (node (ref "R33") (pin "2") (pinfunction "2_2") (pintype "passive"))
      (node (ref "R40") (pin "2") (pinfunction "2_2") (pintype "passive"))
      (node (ref "R41") (pin "2") (pinfunction "2_2") (pintype "passive"))
      (node (ref "R46") (pin "1") (pinfunction "1_1") (pintype "passive"))
      (node (ref "U2") (pin "10") (pinfunction "VDD_10") (pintype "passive"))
      (node (ref "U2") (pin "28") (pinfunction "VDD_28") (pintype "passive"))
    )
    (net (code "81") (name "V6V") (class "Default")
      (node (ref "J4") (pin "3") (pinfunction "3_3") (pintype "passive"))
      (node (ref "Q2") (pin "D") (pinfunction "DRAIN_D") (pintype "passive"))
      (node (ref "R10") (pin "2") (pintype "passive"))
      (node (ref "R11") (pin "2") (pintype "passive"))
      (node (ref "R12") (pin "2") (pintype "passive"))
      (node (ref "R13") (pin "2") (pintype "passive"))
      (node (ref "R2") (pin "2") (pintype "passive"))
      (node (ref "R3") (pin "2") (pintype "passive"))
      (node (ref "R4") (pin "2") (pintype "passive"))
      (node (ref "R47") (pin "2") (pintype "passive"))
      (node (ref "R5") (pin "2") (pintype "passive"))
      (node (ref "R6") (pin "2") (pintype "passive"))
      (node (ref "R7") (pin "2") (pintype "passive"))
      (node (ref "R8") (pin "2") (pintype "passive"))
      (node (ref "R9") (pin "2") (pintype "passive"))
    )
    (net (code "82") (name "VBAT") (class "Default")
      (node (ref "C23") (pin "1") (pinfunction "1_1") (pintype "passive"))
      (node (ref "C24") (pin "1") (pinfunction "1_1") (pintype "passive"))
      (node (ref "D1") (pin "2") (pinfunction "K_2") (pintype "passive"))
      (node (ref "J3") (pin "4") (pinfunction "4_4") (pintype "passive"))
      (node (ref "Q2") (pin "S") (pinfunction "SOURCE_S") (pintype "passive"))
      (node (ref "R16") (pin "1") (pinfunction "1_1") (pintype "passive"))
      (node (ref "R23") (pin "1") (pinfunction "1_1") (pintype "passive"))
      (node (ref "U3") (pin "3") (pinfunction "IN_3") (pintype "passive"))
    )
    (net (code "83") (name "VBUS") (class "Default")
      (node (ref "C21") (pin "1") (pinfunction "1_1") (pintype "passive"))
      (node (ref "D1") (pin "1") (pinfunction "A_1") (pintype "passive"))
      (node (ref "P2") (pin "2") (pinfunction "2_2") (pintype "passive"))
      (node (ref "RW2") (pin "1") (pinfunction "1_1") (pintype "passive"))
    )
    (net (code "84") (name "VDD") (class "Default")
      (node (ref "C1") (pin "2") (pinfunction "2_2") (pintype "passive"))
      (node (ref "C15") (pin "2") (pinfunction "2_2") (pintype "passive"))
      (node (ref "C6") (pin "2") (pinfunction "2_2") (pintype "passive"))
      (node (ref "C8") (pin "2") (pinfunction "2_2") (pintype "passive"))
      (node (ref "C9") (pin "2") (pinfunction "2_2") (pintype "passive"))
      (node (ref "L2") (pin "1") (pinfunction "P1_1") (pintype "passive"))
      (node (ref "U1") (pin "1") (pinfunction "VCCIF_1") (pintype "passive"))
      (node (ref "U1") (pin "22") (pinfunction "VCCMCU_22") (pintype "passive"))
      (node (ref "U1") (pin "31") (pinfunction "VCCRF_31") (pintype "passive"))
    )
    (net (code "85") (name "VDD3V3") (class "Default")
      (node (ref "Q1") (pin "D") (pinfunction "DRAIN_D") (pintype "passive"))
      (node (ref "R20") (pin "2") (pintype "passive"))
      (node (ref "R22") (pin "2") (pinfunction "2_2") (pintype "passive"))
    )
    (net (code "86") (name "unconnected-(U1-VDDSPI-Pad13)") (class "Default")
      (node (ref "U1") (pin "13") (pinfunction "VDDSPI_13") (pintype "passive+no_connect"))
    )
    (net (code "87") (name "unconnected-(U1-XTAL32K-Pad9)") (class "Default")
      (node (ref "U1") (pin "9") (pinfunction "XTAL32K_9") (pintype "passive"))
    )
    (net (code "88") (name "unconnected-(U2-NC-Pad8)") (class "Default")
      (node (ref "U2") (pin "8") (pinfunction "NC_8") (pintype "passive"))
    )
    (net (code "89") (name "unconnected-(U2-NC-Pad14)") (class "Default")
      (node (ref "U2") (pin "14") (pinfunction "NC_14") (pintype "passive"))
    )
    (net (code "90") (name "unconnected-(U2-OUT1-Pad17)") (class "Default")
      (node (ref "U2") (pin "17") (pinfunction "OUT1_17") (pintype "passive"))
    )
    (net (code "91") (name "unconnected-(UB1-Pad3)") (class "Default")
      (node (ref "UB1") (pin "3") (pinfunction "3_3") (pintype "passive"))
    )
    (net (code "92") (name "unconnected-(UB1-Pad7)") (class "Default")
      (node (ref "UB1") (pin "7") (pinfunction "7_7") (pintype "passive"))
    )
  )
)
